# Fonte.net
KiCad netlist of a schematic drawn in EAGLE
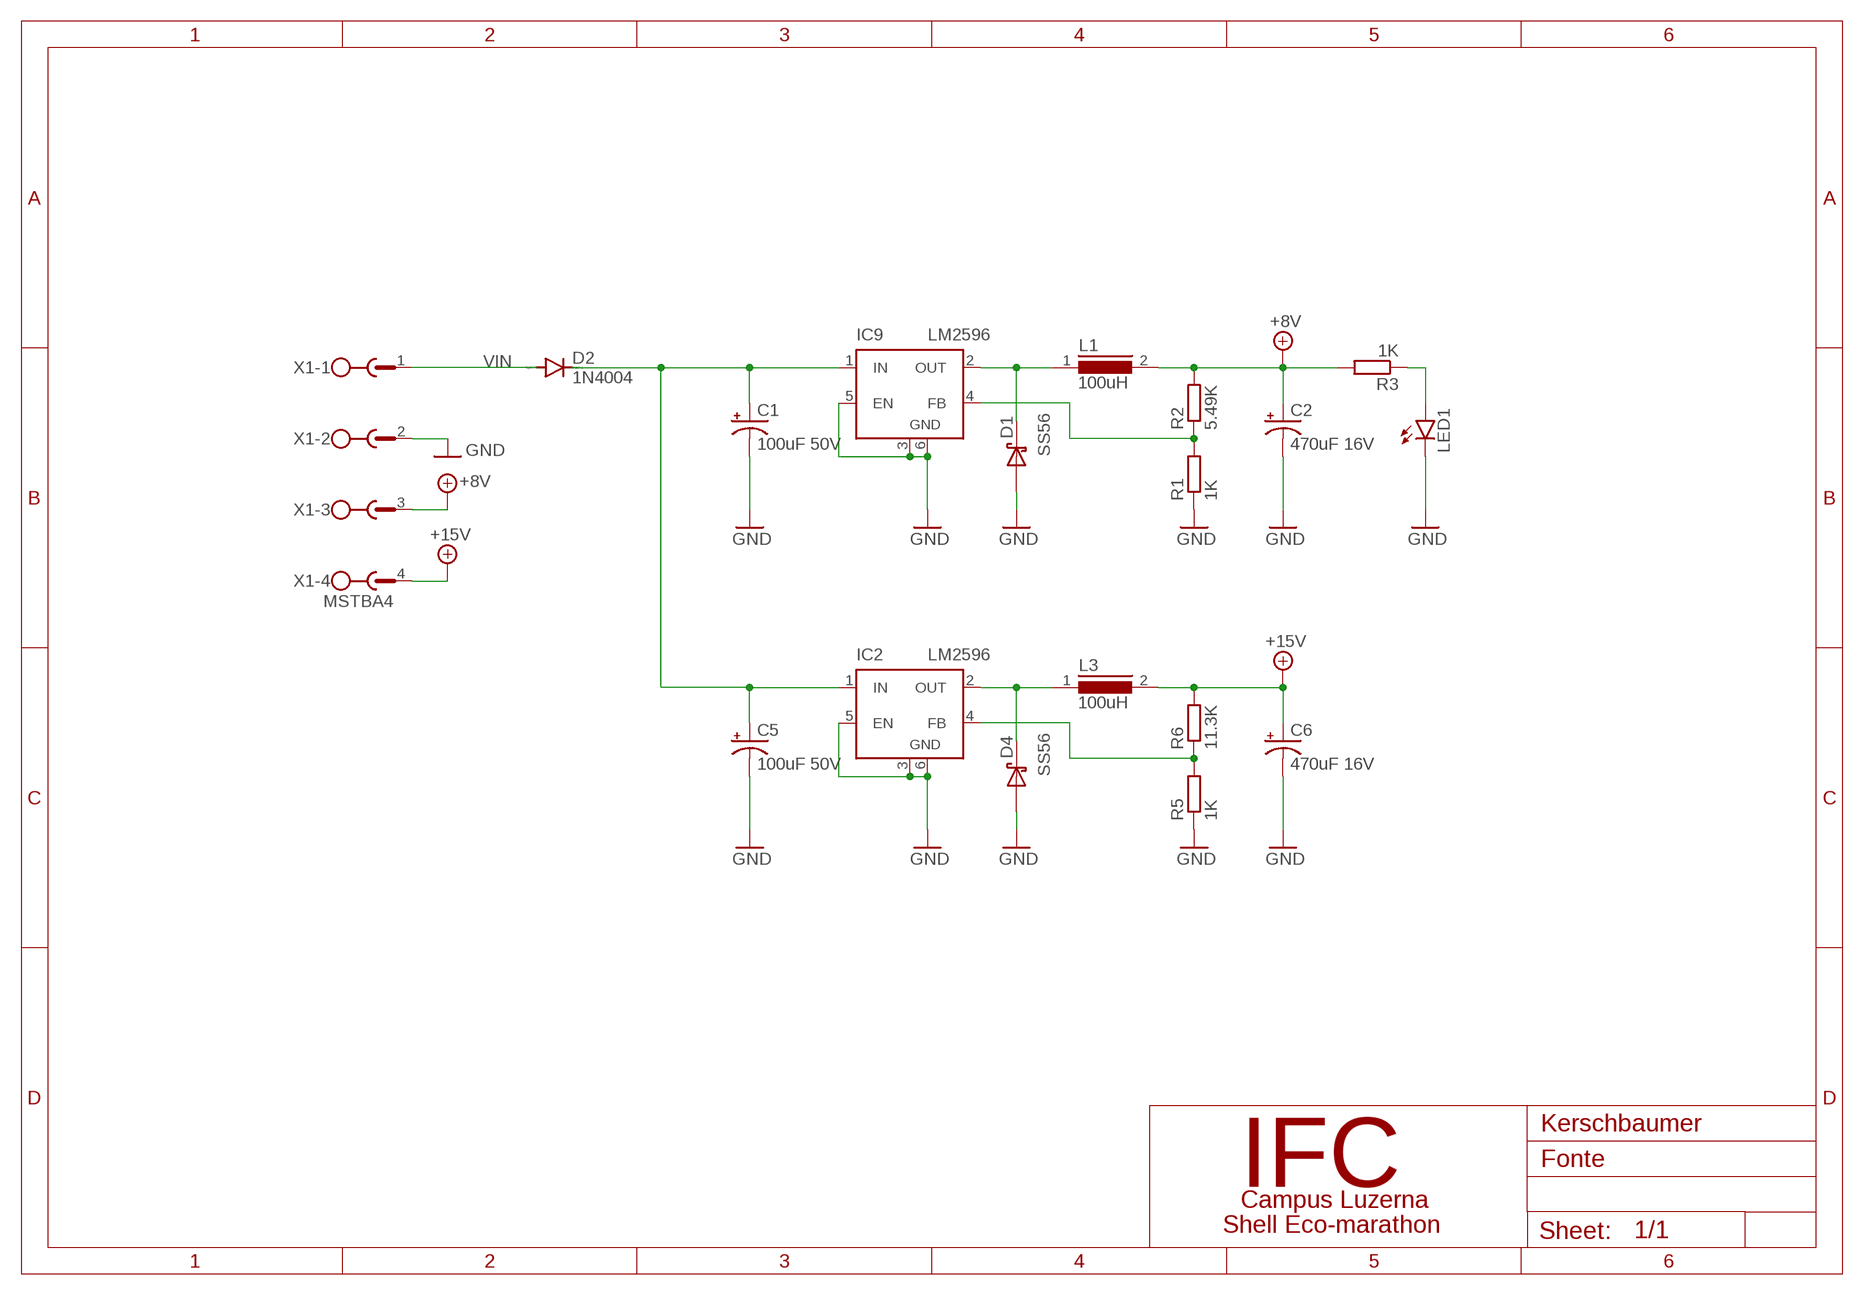
[diagram p0: schematic, sheet 1]

(export (version "E")
  (design (tool "Eeschema 10.0.6"))
  (components
    (comp (ref "C1")
      (value "100uF 50V")
      (footprint "eagle-import:E2,5-7")
      (libsource (lib "eagle-import") (part "CPOL-USE2.5-7"))
    )
    (comp (ref "C2")
      (value "470uF 16V")
      (footprint "eagle-import:E2,5-7")
      (libsource (lib "eagle-import") (part "CPOL-USE2.5-7"))
    )
    (comp (ref "C5")
      (value "100uF 50V")
      (footprint "eagle-import:E2,5-7")
      (libsource (lib "eagle-import") (part "CPOL-USE2.5-7"))
    )
    (comp (ref "C6")
      (value "470uF 16V")
      (footprint "eagle-import:E2,5-7")
      (libsource (lib "eagle-import") (part "CPOL-USE2.5-7"))
    )
    (comp (ref "D1")
      (value "SS56")
      (footprint "eagle-import:SMA-DIODE")
      (libsource (lib "eagle-import") (part "DIODE-SCHOTTKY_"))
    )
    (comp (ref "D2")
      (value "1N4004")
      (footprint "eagle-import:DO41-10")
      (libsource (lib "eagle-import") (part "1N4004"))
    )
    (comp (ref "D4")
      (value "SS56")
      (footprint "eagle-import:SMA-DIODE")
      (libsource (lib "eagle-import") (part "DIODE-SCHOTTKY_"))
    )
    (comp (ref "IC2")
      (value "LM2596")
      (footprint "eagle-import:TO263-5")
      (libsource (lib "eagle-import") (part "LM2596S"))
    )
    (comp (ref "IC9")
      (value "LM2596")
      (footprint "eagle-import:TO263-5")
      (libsource (lib "eagle-import") (part "LM2596S"))
    )
    (comp (ref "L1")
      (value "100uH")
      (footprint "eagle-import:DR125")
      (libsource (lib "eagle-import") (part "DR125"))
    )
    (comp (ref "L3")
      (value "100uH")
      (footprint "eagle-import:DR125")
      (libsource (lib "eagle-import") (part "DR125"))
    )
    (comp (ref "LED1")
      (value "LED3MM")
      (footprint "eagle-import:LED3MM")
      (libsource (lib "eagle-import") (part "LED3MM"))
    )
    (comp (ref "R1")
      (value "1K")
      (footprint "eagle-import:0207_7")
      (libsource (lib "eagle-import") (part "R-EU_0207/7"))
    )
    (comp (ref "R2")
      (value "5.49K")
      (footprint "eagle-import:0207_7")
      (libsource (lib "eagle-import") (part "R-EU_0207/7"))
    )
    (comp (ref "R3")
      (value "1K")
      (footprint "eagle-import:0207_7")
      (libsource (lib "eagle-import") (part "R-EU_0207/7"))
    )
    (comp (ref "R5")
      (value "1K")
      (footprint "eagle-import:0207_7")
      (libsource (lib "eagle-import") (part "R-EU_0207/7"))
    )
    (comp (ref "R6")
      (value "11.3K")
      (footprint "eagle-import:0207_7")
      (libsource (lib "eagle-import") (part "R-EU_0207/7"))
    )
    (comp (ref "X1")
      (value "MSTBA4")
      (footprint "eagle-import:MSTBA4")
      (fields (field (name "MF") "FARNELL") (field (name "MPN") "1757268"))
      (libsource (lib "eagle-import") (part "MSTBA4"))
    )
  )
  (nets
    (net (code "1") (name "+8V") (class "Default")
      (node (ref "C2") (pin "+") (pinfunction "+_+") (pintype "passive"))
      (node (ref "L1") (pin "2") (pinfunction "2_2") (pintype "passive"))
      (node (ref "R2") (pin "2") (pinfunction "2_2") (pintype "passive"))
      (node (ref "R3") (pin "2") (pinfunction "2_2") (pintype "passive"))
      (node (ref "X1") (pin "3") (pinfunction "1_3") (pintype "passive"))
    )
    (net (code "2") (name "+15V") (class "Default")
      (node (ref "C6") (pin "+") (pinfunction "+_+") (pintype "passive"))
      (node (ref "L3") (pin "2") (pinfunction "2_2") (pintype "passive"))
      (node (ref "R6") (pin "2") (pinfunction "2_2") (pintype "passive"))
      (node (ref "X1") (pin "4") (pinfunction "1_4") (pintype "passive"))
    )
    (net (code "3") (name "/VIN") (class "Default")
      (node (ref "D2") (pin "A") (pinfunction "A_A") (pintype "passive"))
      (node (ref "X1") (pin "1") (pinfunction "1_1") (pintype "passive"))
    )
    (net (code "4") (name "GND") (class "Default")
      (node (ref "C1") (pin "-") (pinfunction "-_-") (pintype "passive"))
      (node (ref "C2") (pin "-") (pinfunction "-_-") (pintype "passive"))
      (node (ref "C5") (pin "-") (pinfunction "-_-") (pintype "passive"))
      (node (ref "C6") (pin "-") (pinfunction "-_-") (pintype "passive"))
      (node (ref "D1") (pin "A") (pinfunction "A_A") (pintype "passive"))
      (node (ref "D4") (pin "A") (pinfunction "A_A") (pintype "passive"))
      (node (ref "IC2") (pin "3") (pinfunction "GND_3") (pintype "power_in"))
      (node (ref "IC2") (pin "5") (pinfunction "EN_5") (pintype "input"))
      (node (ref "IC2") (pin "6") (pinfunction "GND_6") (pintype "power_in"))
      (node (ref "IC9") (pin "3") (pinfunction "GND_3") (pintype "power_in"))
      (node (ref "IC9") (pin "5") (pinfunction "EN_5") (pintype "input"))
      (node (ref "IC9") (pin "6") (pinfunction "GND_6") (pintype "power_in"))
      (node (ref "LED1") (pin "K") (pinfunction "C_K") (pintype "passive"))
      (node (ref "R1") (pin "1") (pinfunction "1_1") (pintype "passive"))
      (node (ref "R5") (pin "1") (pinfunction "1_1") (pintype "passive"))
      (node (ref "X1") (pin "2") (pinfunction "1_2") (pintype "passive"))
    )
    (net (code "5") (name "Net-(IC2-FB)") (class "Default")
      (node (ref "IC2") (pin "4") (pinfunction "FB_4") (pintype "input"))
      (node (ref "R5") (pin "2") (pinfunction "2_2") (pintype "passive"))
      (node (ref "R6") (pin "1") (pinfunction "1_1") (pintype "passive"))
    )
    (net (code "6") (name "Net-(IC2-IN)") (class "Default")
      (node (ref "C1") (pin "+") (pinfunction "+_+") (pintype "passive"))
      (node (ref "C5") (pin "+") (pinfunction "+_+") (pintype "passive"))
      (node (ref "D2") (pin "C") (pinfunction "C_C") (pintype "passive"))
      (node (ref "IC2") (pin "1") (pinfunction "IN_1") (pintype "input"))
      (node (ref "IC9") (pin "1") (pinfunction "IN_1") (pintype "input"))
    )
    (net (code "7") (name "Net-(IC2-OUT)") (class "Default")
      (node (ref "D4") (pin "C") (pinfunction "C_C") (pintype "passive"))
      (node (ref "IC2") (pin "2") (pinfunction "OUT_2") (pintype "output"))
      (node (ref "L3") (pin "1") (pinfunction "1_1") (pintype "passive"))
    )
    (net (code "8") (name "Net-(IC9-FB)") (class "Default")
      (node (ref "IC9") (pin "4") (pinfunction "FB_4") (pintype "input"))
      (node (ref "R1") (pin "2") (pinfunction "2_2") (pintype "passive"))
      (node (ref "R2") (pin "1") (pinfunction "1_1") (pintype "passive"))
    )
    (net (code "9") (name "Net-(IC9-OUT)") (class "Default")
      (node (ref "D1") (pin "C") (pinfunction "C_C") (pintype "passive"))
      (node (ref "IC9") (pin "2") (pinfunction "OUT_2") (pintype "output"))
      (node (ref "L1") (pin "1") (pinfunction "1_1") (pintype "passive"))
    )
    (net (code "10") (name "Net-(LED1-PadA)") (class "Default")
      (node (ref "LED1") (pin "A") (pinfunction "A_A") (pintype "passive"))
      (node (ref "R3") (pin "1") (pinfunction "1_1") (pintype "passive"))
    )
  )
)
